# 12-RS485.net
KiCad netlist of a schematic drawn in Altium Designer
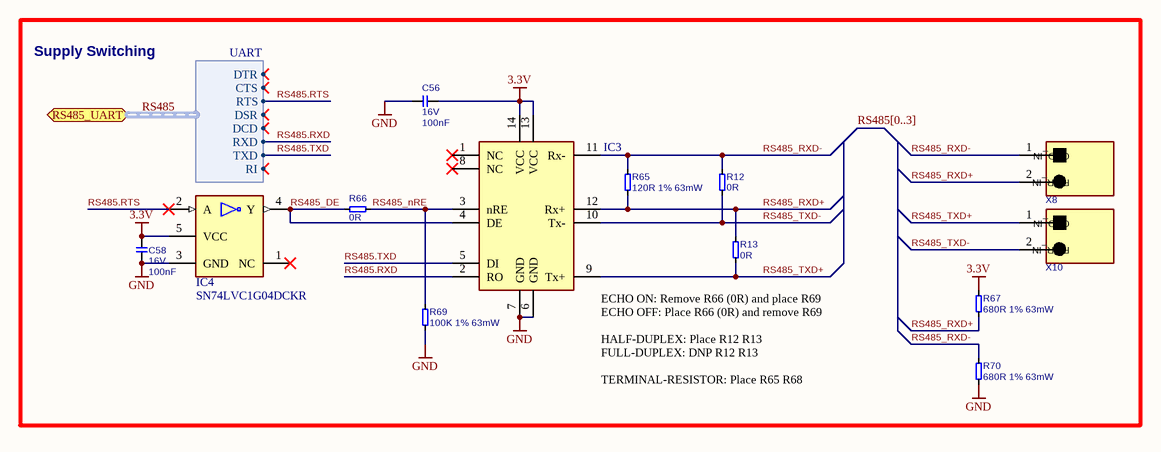
[diagram p0: 12-RS485.SchDoc]

(export (version "E")
  (design (tool "Eeschema 10.0.6"))
  (components
    (comp (ref "C56")
      (value "100nF")
      (footprint "CAPC1005X60N")
      (description "Capacitor Ceramic X7R 100nF 16V 10% 0603")
      (fields
        (field (name "TOLERANCE") "10%")
        (field (name "RATING") "16V")
        (field (name "Comment") "100nF 16V 10% X7R")
      )
      (libsource (lib "AI Gateway - Carrier") (part "C-100nF-16V-10%-0603"))
    )
    (comp (ref "C58")
      (value "100nF")
      (footprint "CAPC1005X60N")
      (description "Capacitor Ceramic X7R 100nF 16V 10% 0603")
      (fields
        (field (name "TOLERANCE") "10%")
        (field (name "RATING") "16V")
        (field (name "Comment") "100nF 16V 10% X7R")
      )
      (libsource (lib "AI Gateway - Carrier") (part "C-100nF-16V-10%-0603"))
    )
    (comp (ref "IC3")
      (value "ISL83491IBZ-T")
      (footprint "SOIC127P600X175-14N")
      (description "Transceptor 1/1 Completo RS422, RS485 14-SOIC")
      (fields (field (name "MFG") "Renesas Electronics America Inc"))
      (libsource (lib "AIGateway") (part "IC-Renesas-ISL83491IBZ-T"))
    )
    (comp (ref "IC4")
      (value "SN74LVC1G04DCKR")
      (footprint "SOT65P210X110-5N")
      (description "IC INVERTER 1CH 1-INP SC70-5")
      (fields (field (name "MFG") "Texas Instruments") (field (name "SYMBOL CHECKED") "M - D"))
      (libsource (lib "AI Gateway - Carrier") (part "IC-TI-SN74LVC1G04"))
    )
    (comp (ref "R12")
      (value "0R")
      (footprint "RESC1005X40N")
      (description "Resistor 0ohm 0402")
      (fields (field (name "POWER") "?") (field (name "TOLERANCE") "1%"))
      (libsource (lib "AI Gateway - Carrier") (part "R-0R-0402"))
    )
    (comp (ref "R13")
      (value "0R")
      (footprint "RESC1005X40N")
      (description "Resistor 0ohm 0402")
      (fields (field (name "POWER") "?") (field (name "TOLERANCE") "1%"))
      (libsource (lib "AI Gateway - Carrier") (part "R-0R-0402"))
    )
    (comp (ref "R65")
      (value "120R 1% 63mW")
      (footprint "RESC1005X40N")
      (description "Resistor 120ohm 63mW 1% 0402")
      (fields (field (name "POWER") "63mW") (field (name "TOLERANCE") "1%"))
      (libsource (lib "AI Gateway - Carrier") (part "R-120R-1%-0402"))
    )
    (comp (ref "R66")
      (value "0R")
      (footprint "RESC1005X40N")
      (description "Resistor 0ohm 0402")
      (fields (field (name "POWER") "?") (field (name "TOLERANCE") "1%"))
      (libsource (lib "AI Gateway - Carrier") (part "R-0R-0402"))
    )
    (comp (ref "R67")
      (value "680R 1% 63mW")
      (footprint "RESC1005X40N")
      (description "Resistor 680ohm 63mW 1% 0402")
      (fields (field (name "POWER") "63mW") (field (name "TOLERANCE") "1%"))
      (libsource (lib "AI Gateway - Carrier") (part "R-680R-1%-0402"))
    )
    (comp (ref "R69")
      (value "100K 1% 63mW")
      (footprint "RESC1005X40N")
      (description "Resistor 100Kohm 63mW 1% 0402")
      (fields (field (name "POWER") "63mW") (field (name "TOLERANCE") "1%"))
      (libsource (lib "AI Gateway - Carrier") (part "R-100K-1%-0402"))
    )
    (comp (ref "R70")
      (value "680R 1% 63mW")
      (footprint "RESC1005X40N")
      (description "Resistor 680ohm 63mW 1% 0402")
      (fields (field (name "POWER") "63mW") (field (name "TOLERANCE") "1%"))
      (libsource (lib "AI Gateway - Carrier") (part "R-680R-1%-0402"))
    )
    (comp (ref "X8")
      (value "1984617")
      (footprint "TERM-BLK-3.5MM")
      (description "2 Position Wire to Board Terminal Block Horizontal with Board 0.138\" (3.50mm) Through Hole")
      (fields (field (name "MFG") "Phoenix Contact"))
      (libsource (lib "Connectors") (part "CON-Phoenix-1984617-1x2-3.5mm"))
    )
    (comp (ref "X10")
      (value "1984617")
      (footprint "TERM-BLK-3.5MM")
      (description "2 Position Wire to Board Terminal Block Horizontal with Board 0.138\" (3.50mm) Through Hole")
      (fields (field (name "MFG") "Phoenix Contact"))
      (libsource (lib "Connectors") (part "CON-Phoenix-1984617-1x2-3.5mm"))
    )
  )
  (nets
    (net (code "6") (name "/RS485.RTS") (class "Default")
      (node (ref "IC4") (pin "2") (pinfunction "A_2") (pintype "input+no_connect"))
    )
    (net (code "7") (name "/RS485.RXD") (class "Default")
      (node (ref "IC3") (pin "2") (pinfunction "RO_2") (pintype "passive"))
    )
    (net (code "8") (name "/RS485.TXD") (class "Default")
      (node (ref "IC3") (pin "5") (pinfunction "DI_5") (pintype "passive"))
    )
    (net (code "10") (name "/RS485_DE") (class "Default")
      (node (ref "IC3") (pin "4") (pinfunction "DE_4") (pintype "passive"))
      (node (ref "IC4") (pin "4") (pinfunction "Y_4") (pintype "output"))
      (node (ref "R66") (pin "2") (pinfunction "2_2") (pintype "passive"))
    )
    (net (code "11") (name "/RS485_RXD+") (class "Default")
      (node (ref "IC3") (pin "12") (pinfunction "Rx+_12") (pintype "passive"))
      (node (ref "R13") (pin "2") (pinfunction "2_2") (pintype "passive"))
      (node (ref "R65") (pin "1") (pinfunction "1_1") (pintype "passive"))
      (node (ref "R67") (pin "1") (pinfunction "1_1") (pintype "passive"))
      (node (ref "X8") (pin "2") (pinfunction "PWR_IN_2") (pintype "passive"))
    )
    (net (code "12") (name "/RS485_RXD-") (class "Default")
      (node (ref "IC3") (pin "11") (pinfunction "Rx-_11") (pintype "passive"))
      (node (ref "R12") (pin "1") (pinfunction "1_1") (pintype "passive"))
      (node (ref "R65") (pin "2") (pinfunction "2_2") (pintype "passive"))
      (node (ref "R70") (pin "2") (pinfunction "2_2") (pintype "passive"))
      (node (ref "X8") (pin "1") (pinfunction "GND_IN_1") (pintype "passive"))
    )
    (net (code "13") (name "/RS485_TXD+") (class "Default")
      (node (ref "IC3") (pin "9") (pinfunction "Tx+_9") (pintype "passive"))
      (node (ref "R13") (pin "1") (pinfunction "1_1") (pintype "passive"))
      (node (ref "X10") (pin "1") (pinfunction "GND_IN_1") (pintype "passive"))
    )
    (net (code "14") (name "/RS485_TXD-") (class "Default")
      (node (ref "IC3") (pin "10") (pinfunction "Tx-_10") (pintype "passive"))
      (node (ref "R12") (pin "2") (pinfunction "2_2") (pintype "passive"))
      (node (ref "X10") (pin "2") (pinfunction "PWR_IN_2") (pintype "passive"))
    )
    (net (code "15") (name "/RS485_nRE") (class "Default")
      (node (ref "IC3") (pin "3") (pinfunction "nRE_3") (pintype "passive"))
      (node (ref "R66") (pin "1") (pinfunction "1_1") (pintype "passive"))
      (node (ref "R69") (pin "2") (pinfunction "2_2") (pintype "passive"))
    )
    (net (code "17") (name "3.3V") (class "Default")
      (node (ref "C56") (pin "1") (pinfunction "1_1") (pintype "passive"))
      (node (ref "C58") (pin "2") (pinfunction "2_2") (pintype "passive"))
      (node (ref "IC3") (pin "13") (pinfunction "VCC_13") (pintype "passive"))
      (node (ref "IC3") (pin "14") (pinfunction "VCC_14") (pintype "passive"))
      (node (ref "IC4") (pin "5") (pinfunction "VCC_5") (pintype "power_in"))
      (node (ref "R67") (pin "2") (pinfunction "2_2") (pintype "passive"))
    )
    (net (code "18") (name "GND") (class "Default")
      (node (ref "C56") (pin "2") (pinfunction "2_2") (pintype "passive"))
      (node (ref "C58") (pin "1") (pinfunction "1_1") (pintype "passive"))
      (node (ref "IC3") (pin "6") (pinfunction "GND_6") (pintype "passive"))
      (node (ref "IC3") (pin "7") (pinfunction "GND_7") (pintype "passive"))
      (node (ref "IC4") (pin "3") (pinfunction "GND_3") (pintype "power_in"))
      (node (ref "R69") (pin "1") (pinfunction "1_1") (pintype "passive"))
      (node (ref "R70") (pin "1") (pinfunction "1_1") (pintype "passive"))
    )
    (net (code "19") (name "unconnected-(IC3-NC-Pad1)") (class "Default")
      (node (ref "IC3") (pin "1") (pinfunction "NC_1") (pintype "passive+no_connect"))
    )
    (net (code "20") (name "unconnected-(IC3-NC-Pad8)") (class "Default")
      (node (ref "IC3") (pin "8") (pinfunction "NC_8") (pintype "passive+no_connect"))
    )
    (net (code "21") (name "unconnected-(IC4-NC-Pad1)") (class "Default")
      (node (ref "IC4") (pin "1") (pinfunction "NC_1") (pintype "passive+no_connect"))
    )
  )
)
